# 03_-_General_Part.net
KiCad netlist of a schematic drawn in Altium Designer
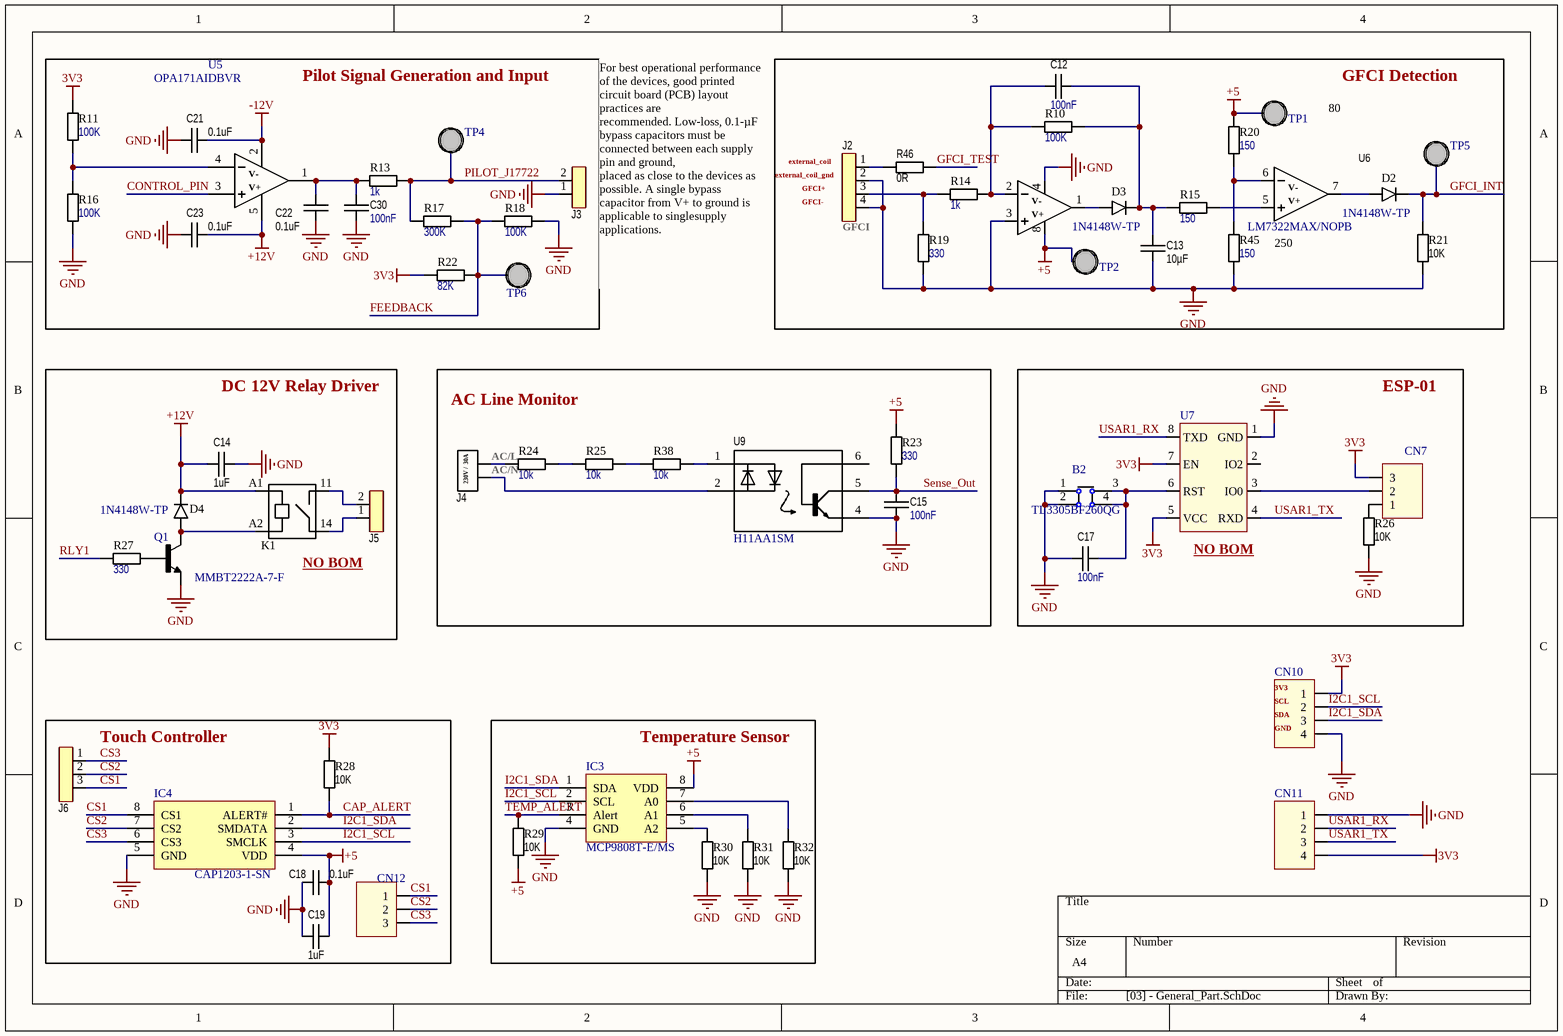
[diagram p0: [03] - General_Part.SchDoc]

(export (version "E")
  (design (tool "Eeschema 10.0.6"))
  (components
    (comp (ref "B2")
      (value "TL3305BF260QG")
      (footprint "Switch")
      (description "Tactile Switch SPST-NO Top Actuated Surface Mount")
      (fields (field (name "MANUFACTURER") "E-Switch"))
      (libsource (lib "myLibrary") (part "SWITCH"))
    )
    (comp (ref "C12")
      (value "100nF")
      (footprint "CAP 0603/1608")
      (description "1µF ±10% 16V Ceramic Capacitor X5R 0603 (1608 Metric)")
      (fields (field (name "PARTNUMBER") "CC0603KRX5R7BB105") (field (name "MANUFACTURER") "Yageo"))
      (libsource (lib "myLibrary") (part "CAPC_100NF_0603_50V"))
    )
    (comp (ref "C13")
      (value "10µF")
      (footprint "CAP 0603/1608")
      (description "10µF ±20% 25V Ceramic Capacitor X5R 0603 (1608 Metric)")
      (fields
        (field (name "PARTNUMBER") "GRM188R61E106MA73D")
        (field (name "MANUFACTURER") "Murata Electronics")
      )
      (libsource (lib "myLibrary") (part "CAPC_10uF_0603_25V"))
    )
    (comp (ref "C14")
      (value "1uF")
      (footprint "CAP 0603/1608")
      (description "1µF ±20% 25V Ceramic Capacitor X5R 0603 (1608 Metric)")
      (fields (field (name "PARTNUMBER") "TMK107BLD105MA-T") (field (name "MANUFACTURER") "Taiyo Yuden"))
      (libsource (lib "myLibrary") (part "CAPC_1uF_0603_25V"))
    )
    (comp (ref "C15")
      (value "100nF")
      (footprint "CAP 0603/1608")
      (description "1µF ±10% 16V Ceramic Capacitor X5R 0603 (1608 Metric)")
      (fields (field (name "PARTNUMBER") "CC0603KRX5R7BB105") (field (name "MANUFACTURER") "Yageo"))
      (libsource (lib "myLibrary") (part "CAPC_100NF_0603_50V"))
    )
    (comp (ref "C17")
      (value "100nF")
      (footprint "CAP 0603/1608")
      (description "1µF ±10% 16V Ceramic Capacitor X5R 0603 (1608 Metric)")
      (fields (field (name "PARTNUMBER") "CC0603KRX5R7BB105") (field (name "MANUFACTURER") "Yageo"))
      (libsource (lib "myLibrary") (part "CAPC_100NF_0603_50V"))
    )
    (comp (ref "C18")
      (value "0.1uF")
      (footprint "CAP 0603/1608")
      (description "0.1µF ±20% 50V Ceramic Capacitor X7R 0603 (1608 Metric)")
      (fields (field (name "PARTNUMBER") "C0603C104M5RACTU") (field (name "MANUFACTURER") "KEMET"))
      (libsource (lib "myLibrary") (part "CAPC_0.1uF_0603_50V"))
    )
    (comp (ref "C19")
      (value "1uF")
      (footprint "CAP 0603/1608")
      (description "1µF ±20% 25V Ceramic Capacitor X5R 0603 (1608 Metric)")
      (fields (field (name "PARTNUMBER") "TMK107BLD105MA-T") (field (name "MANUFACTURER") "Taiyo Yuden"))
      (libsource (lib "myLibrary") (part "CAPC_1uF_0603_25V"))
    )
    (comp (ref "C21")
      (value "0.1uF")
      (footprint "CAP 0603/1608")
      (description "0.1µF ±20% 50V Ceramic Capacitor X7R 0603 (1608 Metric)")
      (fields (field (name "PARTNUMBER") "C0603C104M5RACTU") (field (name "MANUFACTURER") "KEMET"))
      (libsource (lib "myLibrary") (part "CAPC_0.1uF_0603_50V"))
    )
    (comp (ref "C22")
      (value "0.1uF")
      (footprint "CAP 0603/1608")
      (description "0.1µF ±20% 50V Ceramic Capacitor X7R 0603 (1608 Metric)")
      (fields (field (name "PARTNUMBER") "C0603C104M5RACTU") (field (name "MANUFACTURER") "KEMET"))
      (libsource (lib "myLibrary") (part "CAPC_0.1uF_0603_50V"))
    )
    (comp (ref "C23")
      (value "0.1uF")
      (footprint "CAP 0603/1608")
      (description "0.1µF ±20% 50V Ceramic Capacitor X7R 0603 (1608 Metric)")
      (fields (field (name "PARTNUMBER") "C0603C104M5RACTU") (field (name "MANUFACTURER") "KEMET"))
      (libsource (lib "myLibrary") (part "CAPC_0.1uF_0603_50V"))
    )
    (comp (ref "C30")
      (value "100nF")
      (footprint "CAP 0603/1608")
      (description "1µF ±10% 16V Ceramic Capacitor X5R 0603 (1608 Metric)")
      (fields (field (name "PARTNUMBER") "CC0603KRX5R7BB105") (field (name "MANUFACTURER") "Yageo"))
      (libsource (lib "myLibrary") (part "CAPC_100NF_0603_50V"))
    )
    (comp (ref "CN7")
      (value "87220-3")
      (footprint "Terminal_3")
      (description "Connector Header Through Hole 3 position 0.100\" (2.54mm)")
      (fields (field (name "MANUFACTURER") "TE Connectivity AMP Connectors"))
      (libsource (lib "") (part "CONN_3POS_1"))
    )
    (comp (ref "CN10")
      (value "61300411121")
      (footprint "Terminal_4")
      (description "Connector Header Through Hole 4 position 0.100\" (2.54mm)")
      (fields (field (name "MANUFACTURER") "Wurth Electronics Inc."))
      (libsource (lib "myLibrary") (part "CONN_4POS"))
    )
    (comp (ref "CN11")
      (value "61300411121")
      (footprint "Terminal_4")
      (description "Connector Header Through Hole 4 position 0.100\" (2.54mm)")
      (fields (field (name "MANUFACTURER") "Wurth Electronics Inc."))
      (libsource (lib "myLibrary") (part "CONN_4POS"))
    )
    (comp (ref "CN12")
      (value "87220-3")
      (footprint "Terminal_3")
      (description "Connector Header Through Hole 3 position 0.100\" (2.54mm)")
      (fields (field (name "MANUFACTURER") "TE Connectivity AMP Connectors"))
      (libsource (lib "myLibrary") (part "CONN_3POS"))
    )
    (comp (ref "D2")
      (value "1N4148W-TP")
      (footprint "SOD123")
      (description "Diode Standard 100V 150mA Surface Mount SOD-123")
      (fields (field (name "MANUFACTURER") "Micro Commercial Co"))
      (libsource (lib "myLibrary") (part "DIODE _100V_150MA"))
    )
    (comp (ref "D3")
      (value "1N4148W-TP")
      (footprint "SOD123")
      (description "Diode Standard 100V 150mA Surface Mount SOD-123")
      (fields (field (name "MANUFACTURER") "Micro Commercial Co"))
      (libsource (lib "myLibrary") (part "DIODE _100V_150MA"))
    )
    (comp (ref "D4")
      (value "1N4148W-TP")
      (footprint "SOD123")
      (description "Diode Standard 100V 150mA Surface Mount SOD-123")
      (fields (field (name "MANUFACTURER") "Micro Commercial Co"))
      (libsource (lib "myLibrary") (part "DIODE _100V_150MA"))
    )
    (comp (ref "IC3")
      (value "MCP9808T-E/MS")
      (footprint "MSOP-8")
      (description "Temperature Sensor Digital, Local -40°C ~ 125°C 10 b 8-MSOP")
      (fields (field (name "MANUFACTURER") "Microchip Technology"))
      (libsource (lib "myLibrary") (part "MCP9808"))
    )
    (comp (ref "IC4")
      (value "CAP1203-1-SN")
      (footprint "SOIC-8")
      (description "Capacitive Touch Buttons 8-SOIC")
      (fields (field (name "MANUFACTURER") "Microchip Technology"))
      (libsource (lib "myLibrary") (part "CAP1203"))
    )
    (comp (ref "J2")
      (value "1985218")
      (footprint "BLK_04P_3.5MM")
      (description "4 Position Wire to Board Terminal Block 45° (135°) Angle with Board 0.138\" (3.50mm) Through Hole")
      (fields (field (name "MANUFACTURER") "Phoenix Contact"))
      (libsource (lib "myLibrary") (part "BLK_04_3.5"))
    )
    (comp (ref "J3")
      (value "1985195")
      (footprint "BLK_02P_3.5MM")
      (description "2 Position Wire to Board Terminal Block 45° (135°) Angle with Board 0.138\" (3.50mm) Through Hole")
      (fields (field (name "MANUFACTURER") "Phoenix Contact"))
      (libsource (lib "myLibrary") (part "BLK_02_3.5"))
    )
    (comp (ref "J4")
      (value "1868076")
      (footprint "30Amp_Connector")
      (description "2 Position Wire to Board Terminal Block Horizontal with Board 0.300\" (7.62mm) Through Hole")
      (fields (field (name "MANUFACTURER") "Phoenix Contact"))
      (libsource (lib "myLibrary") (part "TERM_BLK_02_30A"))
    )
    (comp (ref "J5")
      (value "1985195")
      (footprint "BLK_02P_3.5MM")
      (description "2 Position Wire to Board Terminal Block 45° (135°) Angle with Board 0.138\" (3.50mm) Through Hole")
      (fields (field (name "MANUFACTURER") "Phoenix Contact"))
      (libsource (lib "myLibrary") (part "BLK_02_3.5"))
    )
    (comp (ref "J6")
      (value "1995279")
      (footprint "BLK_03P_3.5MM")
      (description "3 Position Wire to Board Terminal Block 45° (135°) Angle with Board 0.138\" (3.50mm) Through Hole")
      (fields (field (name "MANUFACTURER") "Phoenix Contact"))
      (libsource (lib "myLibrary") (part "BLK_03_3.5"))
    )
    (comp (ref "K1")
      (value "PCN-112D3MHZ,000")
      (footprint "Relay_PCN")
      (description "General Purpose Relay SPST-NO (1 Form A) 12VDC Coil Through Hole")
      (fields (field (name "MANUFACTURER") "TE Connectivity Potter & Brumfield Relays"))
      (libsource (lib "myLibrary") (part "RL_PCN"))
    )
    (comp (ref "Q1")
      (value "MMBT2222A-7-F")
      (footprint "SOT23-3")
      (description "Bipolar (BJT) Transistor NPN 40V 600mA 300MHz 310mW Surface Mount SOT-23-3")
      (fields (field (name "MANUFACTURER") "Diodes Incorporated"))
      (libsource (lib "myLibrary") (part "NPN_40V_0.6A"))
    )
    (comp (ref "R10")
      (value "100K")
      (footprint "R0603")
      (description "100 kOhms ±0.1% 0.1W, 1/10W Chip Resistor 0603 (1608 Metric) Thin Film")
      (fields (field (name "PARTNUMBER") "RT0603BRD07100KL") (field (name "MANUFACTURER") "Yageo"))
      (libsource (lib "") (part "RES_100k_0603_0.1%_1"))
    )
    (comp (ref "R11")
      (value "100K")
      (footprint "R0603")
      (description "100 kOhms ±0.1% 0.1W, 1/10W Chip Resistor 0603 (1608 Metric) Thin Film")
      (fields (field (name "PARTNUMBER") "RT0603BRD07100KL") (field (name "MANUFACTURER") "Yageo"))
      (libsource (lib "myLibrary") (part "RES_100k_0603_0.1%"))
    )
    (comp (ref "R13")
      (value "1k")
      (footprint "R0603")
      (description "1 kOhms ±5% 0.1W, 1/10W Chip Resistor 0603 (1608 Metric) Moisture Resistant Thick Film\r\nDo")
      (fields (field (name "PARTNUMBER") "RC0603JR-071KL") (field (name "MANUFACTURER") "Yageo"))
      (libsource (lib "myLibrary") (part "RES_1k_0603_5%"))
    )
    (comp (ref "R14")
      (value "1k")
      (footprint "R0603")
      (description "1 kOhms ±5% 0.1W, 1/10W Chip Resistor 0603 (1608 Metric) Moisture Resistant Thick Film\r\nDo")
      (fields (field (name "PARTNUMBER") "RC0603JR-071KL") (field (name "MANUFACTURER") "Yageo"))
      (libsource (lib "myLibrary") (part "RES_1k_0603_5%"))
    )
    (comp (ref "R15")
      (value "150")
      (footprint "R0603")
      (description "150 Ohms ±5% 0.1W, 1/10W Chip Resistor 0603 (1608 Metric) Moisture Resistant Thick Film")
      (fields (field (name "PARTNUMBER") "RC0603JR-07150RL") (field (name "MANUFACTURER") "Yageo"))
      (libsource (lib "myLibrary") (part "RES_150_0603_5%"))
    )
    (comp (ref "R16")
      (value "100K")
      (footprint "R0603")
      (description "100 kOhms ±0.1% 0.1W, 1/10W Chip Resistor 0603 (1608 Metric) Thin Film")
      (fields (field (name "PARTNUMBER") "RT0603BRD07100KL") (field (name "MANUFACTURER") "Yageo"))
      (libsource (lib "myLibrary") (part "RES_100k_0603_0.1%"))
    )
    (comp (ref "R17")
      (value "300K")
      (footprint "R0603")
      (description "300 kOhms ±5% 0.1W, 1/10W Chip Resistor 0603 (1608 Metric) Moisture Resistant Thick Film")
      (fields (field (name "PARTNUMBER") "RC0603JR-07300KL") (field (name "MANUFACTURER") "Yageo"))
      (libsource (lib "myLibrary") (part "RES_300K_0603_1%"))
    )
    (comp (ref "R18")
      (value "100K")
      (footprint "R0603")
      (description "100 kOhms ±0.1% 0.1W, 1/10W Chip Resistor 0603 (1608 Metric) Thin Film")
      (fields (field (name "PARTNUMBER") "RT0603BRD07100KL") (field (name "MANUFACTURER") "Yageo"))
      (libsource (lib "") (part "RES_100k_0603_0.1%_1"))
    )
    (comp (ref "R19")
      (value "330")
      (footprint "R0603")
      (description "330 Ohms ±1% 0.1W, 1/10W Chip Resistor 0603 (1608 Metric) Moisture Resistant Thick Film")
      (fields (field (name "PARTNUMBER") "RC0603FR-07330RL") (field (name "MANUFACTURER") "Yageo"))
      (libsource (lib "") (part "RES_330_0603_1%_1"))
    )
    (comp (ref "R20")
      (value "150")
      (footprint "R0603")
      (description "150 Ohms ±5% 0.1W, 1/10W Chip Resistor 0603 (1608 Metric) Moisture Resistant Thick Film")
      (fields (field (name "PARTNUMBER") "RC0603JR-07150RL") (field (name "MANUFACTURER") "Yageo"))
      (libsource (lib "") (part "RES_150_0603_5%_1"))
    )
    (comp (ref "R21")
      (value "10K")
      (footprint "R0603")
      (fields (field (name "PARTNUMBER") "ESR03EZPF1002") (field (name "MANUFACTURER") "Rohm Semiconductor"))
      (libsource (lib "myLibrary") (part "RES_10K"))
    )
    (comp (ref "R22")
      (value "82K")
      (footprint "R0603")
      (description "82 kOhms ±0.1% 0.1W, 1/10W Chip Resistor 0603 (1608 Metric) Thin Film")
      (fields (field (name "PARTNUMBER") "RT0603BRD0782KL") (field (name "MANUFACTURER") "Yageo"))
      (libsource (lib "myLibrary") (part "RES_82K_0603_0.1%"))
    )
    (comp (ref "R23")
      (value "330")
      (footprint "R0603")
      (description "330 Ohms ±1% 0.1W, 1/10W Chip Resistor 0603 (1608 Metric) Moisture Resistant Thick Film")
      (fields (field (name "PARTNUMBER") "RC0603FR-07330RL") (field (name "MANUFACTURER") "Yageo"))
      (libsource (lib "") (part "RES_330_0603_1%_1"))
    )
    (comp (ref "R24")
      (value "10k")
      (footprint "R1206")
      (description "10 kOhms ±1% 0.25W, 1/4W Chip Resistor 1206 (3216 Metric) Automotive AEC-Q200 Thick Film")
      (fields
        (field (name "PARTNUMBER") "ERJ-8ENF1002V")
        (field (name "MANUFACTURER") "Panasonic Electronic Components")
      )
      (libsource (lib "myLibrary") (part "RES_10k_1206_1%"))
    )
    (comp (ref "R25")
      (value "10k")
      (footprint "R1206")
      (description "10 kOhms ±1% 0.25W, 1/4W Chip Resistor 1206 (3216 Metric) Automotive AEC-Q200 Thick Film")
      (fields
        (field (name "PARTNUMBER") "ERJ-8ENF1002V")
        (field (name "MANUFACTURER") "Panasonic Electronic Components")
      )
      (libsource (lib "myLibrary") (part "RES_10k_1206_1%"))
    )
    (comp (ref "R26")
      (value "10K")
      (footprint "R0603")
      (fields (field (name "PARTNUMBER") "ESR03EZPF1002") (field (name "MANUFACTURER") "Rohm Semiconductor"))
      (libsource (lib "") (part "RES_10K_1"))
    )
    (comp (ref "R27")
      (value "330")
      (footprint "R0603")
      (description "330 Ohms ±1% 0.1W, 1/10W Chip Resistor 0603 (1608 Metric) Moisture Resistant Thick Film")
      (fields (field (name "PARTNUMBER") "RC0603FR-07330RL") (field (name "MANUFACTURER") "Yageo"))
      (libsource (lib "myLibrary") (part "RES_330_0603_1%"))
    )
    (comp (ref "R28")
      (value "10K")
      (footprint "R0603")
      (fields (field (name "PARTNUMBER") "ESR03EZPF1002") (field (name "MANUFACTURER") "Rohm Semiconductor"))
      (libsource (lib "myLibrary") (part "RES_10K"))
    )
    (comp (ref "R29")
      (value "10K")
      (footprint "R0603")
      (fields (field (name "PARTNUMBER") "ESR03EZPF1002") (field (name "MANUFACTURER") "Rohm Semiconductor"))
      (libsource (lib "myLibrary") (part "RES_10K"))
    )
    (comp (ref "R30")
      (value "10K")
      (footprint "R0603")
      (fields (field (name "PARTNUMBER") "ESR03EZPF1002") (field (name "MANUFACTURER") "Rohm Semiconductor"))
      (libsource (lib "myLibrary") (part "RES_10K"))
    )
    (comp (ref "R31")
      (value "10K")
      (footprint "R0603")
      (fields (field (name "PARTNUMBER") "ESR03EZPF1002") (field (name "MANUFACTURER") "Rohm Semiconductor"))
      (libsource (lib "myLibrary") (part "RES_10K"))
    )
    (comp (ref "R32")
      (value "10K")
      (footprint "R0603")
      (fields (field (name "PARTNUMBER") "ESR03EZPF1002") (field (name "MANUFACTURER") "Rohm Semiconductor"))
      (libsource (lib "myLibrary") (part "RES_10K"))
    )
    (comp (ref "R38")
      (value "10k")
      (footprint "R1206")
      (description "10 kOhms ±1% 0.25W, 1/4W Chip Resistor 1206 (3216 Metric) Automotive AEC-Q200 Thick Film")
      (fields
        (field (name "PARTNUMBER") "ERJ-8ENF1002V")
        (field (name "MANUFACTURER") "Panasonic Electronic Components")
      )
      (libsource (lib "myLibrary") (part "RES_10k_1206_1%"))
    )
    (comp (ref "R45")
      (value "150")
      (footprint "R0603")
      (description "150 Ohms ±5% 0.1W, 1/10W Chip Resistor 0603 (1608 Metric) Moisture Resistant Thick Film")
      (fields (field (name "PARTNUMBER") "RC0603JR-07150RL") (field (name "MANUFACTURER") "Yageo"))
      (libsource (lib "") (part "RES_150_0603_5%_1"))
    )
    (comp (ref "R46")
      (value "0R")
      (footprint "R0603")
      (description "RES 0R 0603 JUMPER")
      (fields (field (name "PARTNUMBER") "RC0603JR-070RL") (field (name "MANUFACTURER") "Yageo"))
      (libsource (lib "myLibrary") (part "RES_0R_0603_JUMPER"))
    )
    (comp (ref "TP1") (value "Test_Point") (footprint "TP") (libsource (lib "myLibrary") (part "Test_Point")))
    (comp (ref "TP2") (value "Test_Point") (footprint "TP") (libsource (lib "myLibrary") (part "Test_Point")))
    (comp (ref "TP4") (value "Test_Point") (footprint "TP") (libsource (lib "myLibrary") (part "Test_Point")))
    (comp (ref "TP5") (value "Test_Point") (footprint "TP") (libsource (lib "myLibrary") (part "Test_Point")))
    (comp (ref "TP6") (value "Test_Point") (footprint "TP") (libsource (lib "myLibrary") (part "Test_Point")))
    (comp (ref "U5")
      (value "OPA171AIDBVR")
      (footprint "SOT-23-5")
      (description "General Purpose Amplifier 1 Circuit Rail-to-Rail SOT-23-5")
      (fields (field (name "MANUFACTURER") "Texas Instruments"))
      (libsource (lib "myLibrary") (part "OPA171"))
    )
    (comp (ref "U6")
      (value "LM7322MAX/NOPB")
      (footprint "SOIC-8")
      (description "General Purpose Amplifier 2 Circuit Rail-to-Rail 8-SOIC")
      (fields (field (name "MANUFACTURER") "Texas Instruments"))
      (libsource (lib "myLibrary") (part "OP_LM7322"))
    )
    (comp (ref "U7")
      (value "317060016")
      (footprint "Terminal_ESP")
      (description "WiFi 802.11b/g/n Transceiver Module 2.4GHz ~ 2.48GHz Integrated, Trace Through Hole")
      (fields (field (name "MANUFACTURER") "Seeed Technology Co., Ltd"))
      (libsource (lib "myLibrary") (part "ESP-01"))
    )
    (comp (ref "U9")
      (value "H11AA1SM")
      (footprint "6-SMD")
      (description "Optoisolator Transistor with Base Output 4170Vrms 1 Channel 6-SMD")
      (fields (field (name "MANUFACTURER") "ON Semiconductor"))
      (libsource (lib "myLibrary") (part "Opto_H11AA1"))
    )
  )
  (nets
    (net (code "1") (name "+5") (class "Default")
      (node (ref "C18") (pin "2") (pintype "passive"))
      (node (ref "C19") (pin "2") (pintype "passive"))
      (node (ref "IC3") (pin "8") (pinfunction "VDD_8") (pintype "passive"))
      (node (ref "IC4") (pin "4") (pinfunction "VDD_4") (pintype "passive"))
      (node (ref "R20") (pin "1") (pinfunction "1_1") (pintype "passive"))
      (node (ref "R23") (pin "1") (pinfunction "1_1") (pintype "passive"))
      (node (ref "R29") (pin "2") (pinfunction "2_2") (pintype "passive"))
      (node (ref "TP1") (pin "1") (pinfunction "1_1") (pintype "passive"))
      (node (ref "TP2") (pin "1") (pinfunction "1_1") (pintype "passive"))
      (node (ref "U6") (pin "8") (pinfunction "V+_8") (pintype "power_in"))
    )
    (net (code "2") (name "+12V") (class "Default")
      (node (ref "C14") (pin "1") (pintype "passive"))
      (node (ref "C23") (pin "1") (pintype "passive"))
      (node (ref "D4") (pin "C") (pinfunction "C_C") (pintype "passive"))
      (node (ref "K1") (pin "A1") (pinfunction "A1_A1") (pintype "passive"))
      (node (ref "U5") (pin "5") (pinfunction "VDD_5") (pintype "power_in"))
    )
    (net (code "3") (name "-12V") (class "Default")
      (node (ref "C21") (pin "1") (pintype "passive"))
      (node (ref "U5") (pin "2") (pinfunction "GND_2") (pintype "power_in"))
    )
    (net (code "4") (name "/CAP_ALERT") (class "Default")
      (node (ref "IC4") (pin "1") (pinfunction "ALERT#_1") (pintype "passive"))
      (node (ref "R28") (pin "2") (pinfunction "2_2") (pintype "passive"))
    )
    (net (code "5") (name "/CONTROL_PIN") (class "Default")
      (node (ref "U5") (pin "3") (pinfunction "IN+_3") (pintype "passive"))
    )
    (net (code "6") (name "/CS1") (class "Default")
      (node (ref "CN12") (pin "1") (pinfunction "1_1") (pintype "passive"))
      (node (ref "IC4") (pin "8") (pinfunction "CS1_8") (pintype "passive"))
      (node (ref "J6") (pin "3") (pintype "passive"))
    )
    (net (code "7") (name "/CS2") (class "Default")
      (node (ref "CN12") (pin "2") (pinfunction "2_2") (pintype "passive"))
      (node (ref "IC4") (pin "7") (pinfunction "CS2_7") (pintype "passive"))
      (node (ref "J6") (pin "2") (pintype "passive"))
    )
    (net (code "8") (name "/CS3") (class "Default")
      (node (ref "CN12") (pin "3") (pinfunction "3_3") (pintype "passive"))
      (node (ref "IC4") (pin "6") (pinfunction "CS3_6") (pintype "passive"))
      (node (ref "J6") (pin "1") (pintype "passive"))
    )
    (net (code "9") (name "/FEEDBACK") (class "Default")
      (node (ref "R17") (pin "2") (pinfunction "2_2") (pintype "passive"))
      (node (ref "R18") (pin "1") (pinfunction "1_1") (pintype "passive"))
      (node (ref "R22") (pin "2") (pinfunction "2_2") (pintype "passive"))
      (node (ref "TP6") (pin "1") (pinfunction "1_1") (pintype "passive"))
    )
    (net (code "10") (name "/GFCI_INT") (class "Default")
      (node (ref "D2") (pin "C") (pinfunction "C_C") (pintype "passive"))
      (node (ref "R21") (pin "1") (pinfunction "1_1") (pintype "passive"))
      (node (ref "TP5") (pin "1") (pinfunction "1_1") (pintype "passive"))
    )
    (net (code "11") (name "/GFCI_TEST") (class "Default")
      (node (ref "R46") (pin "2") (pinfunction "2_2") (pintype "passive"))
    )
    (net (code "12") (name "/I2C1_SCL") (class "Default")
      (node (ref "CN10") (pin "2") (pinfunction "2_2") (pintype "passive"))
      (node (ref "IC3") (pin "2") (pinfunction "SCL_2") (pintype "passive"))
      (node (ref "IC4") (pin "3") (pinfunction "SMCLK_3") (pintype "passive"))
    )
    (net (code "13") (name "/I2C1_SDA") (class "Default")
      (node (ref "CN10") (pin "3") (pinfunction "3_3") (pintype "passive"))
      (node (ref "IC3") (pin "1") (pinfunction "SDA_1") (pintype "passive"))
      (node (ref "IC4") (pin "2") (pinfunction "SMDATA_2") (pintype "passive"))
    )
    (net (code "14") (name "/PILOT_J17722") (class "Default")
      (node (ref "J3") (pin "2") (pintype "passive"))
      (node (ref "R13") (pin "2") (pinfunction "2_2") (pintype "passive"))
      (node (ref "R17") (pin "1") (pinfunction "1_1") (pintype "passive"))
      (node (ref "TP4") (pin "1") (pinfunction "1_1") (pintype "passive"))
    )
    (net (code "15") (name "/RLY1") (class "Default")
      (node (ref "R27") (pin "1") (pinfunction "1_1") (pintype "passive"))
    )
    (net (code "16") (name "/Sense_Out") (class "Default")
      (node (ref "C15") (pin "1") (pintype "passive"))
      (node (ref "R23") (pin "2") (pinfunction "2_2") (pintype "passive"))
      (node (ref "U9") (pin "5") (pinfunction "C_5") (pintype "passive"))
    )
    (net (code "17") (name "/TEMP_ALERT") (class "Default")
      (node (ref "IC3") (pin "3") (pinfunction "Alert_3") (pintype "passive"))
      (node (ref "R29") (pin "1") (pinfunction "1_1") (pintype "passive"))
    )
    (net (code "18") (name "/USAR1_RX") (class "Default")
      (node (ref "CN11") (pin "2") (pinfunction "2_2") (pintype "passive"))
      (node (ref "U7") (pin "8") (pinfunction "TXD_8") (pintype "passive"))
    )
    (net (code "19") (name "/USAR1_TX") (class "Default")
      (node (ref "CN11") (pin "3") (pinfunction "3_3") (pintype "passive"))
      (node (ref "U7") (pin "4") (pinfunction "RXD_4") (pintype "passive"))
    )
    (net (code "20") (name "3V3") (class "Default")
      (node (ref "CN10") (pin "1") (pinfunction "1_1") (pintype "passive"))
      (node (ref "CN11") (pin "4") (pinfunction "4_4") (pintype "passive"))
      (node (ref "CN7") (pin "3") (pinfunction "3_3") (pintype "passive"))
      (node (ref "R11") (pin "1") (pinfunction "1_1") (pintype "passive"))
      (node (ref "R22") (pin "1") (pinfunction "1_1") (pintype "passive"))
      (node (ref "R28") (pin "1") (pinfunction "1_1") (pintype "passive"))
      (node (ref "U7") (pin "5") (pinfunction "VCC_5") (pintype "passive"))
      (node (ref "U7") (pin "7") (pinfunction "EN_7") (pintype "passive"))
    )
    (net (code "21") (name "GND") (class "Default")
      (node (ref "B2") (pin "1") (pinfunction "1_1") (pintype "passive"))
      (node (ref "B2") (pin "2") (pinfunction "2_2") (pintype "passive"))
      (node (ref "C13") (pin "2") (pintype "passive"))
      (node (ref "C14") (pin "2") (pintype "passive"))
      (node (ref "C15") (pin "2") (pintype "passive"))
      (node (ref "C17") (pin "1") (pintype "passive"))
      (node (ref "C18") (pin "1") (pintype "passive"))
      (node (ref "C19") (pin "1") (pintype "passive"))
      (node (ref "C21") (pin "2") (pintype "passive"))
      (node (ref "C22") (pin "2") (pintype "passive"))
      (node (ref "C23") (pin "2") (pintype "passive"))
      (node (ref "C30") (pin "2") (pintype "passive"))
      (node (ref "CN10") (pin "4") (pinfunction "4_4") (pintype "passive"))
      (node (ref "CN11") (pin "1") (pinfunction "1_1") (pintype "passive"))
      (node (ref "IC3") (pin "4") (pinfunction "GND_4") (pintype "passive"))
      (node (ref "IC4") (pin "5") (pinfunction "GND_5") (pintype "passive"))
      (node (ref "J2") (pin "2") (pintype "passive"))
      (node (ref "J2") (pin "4") (pintype "passive"))
      (node (ref "J3") (pin "1") (pintype "passive"))
      (node (ref "Q1") (pin "E") (pinfunction "E_E") (pintype "passive"))
      (node (ref "R16") (pin "2") (pinfunction "2_2") (pintype "passive"))
      (node (ref "R18") (pin "2") (pinfunction "2_2") (pintype "passive"))
      (node (ref "R19") (pin "2") (pinfunction "2_2") (pintype "passive"))
      (node (ref "R21") (pin "2") (pinfunction "2_2") (pintype "passive"))
      (node (ref "R26") (pin "1") (pinfunction "1_1") (pintype "passive"))
      (node (ref "R30") (pin "2") (pinfunction "2_2") (pintype "passive"))
      (node (ref "R31") (pin "2") (pinfunction "2_2") (pintype "passive"))
      (node (ref "R32") (pin "2") (pinfunction "2_2") (pintype "passive"))
      (node (ref "R45") (pin "2") (pinfunction "2_2") (pintype "passive"))
      (node (ref "U6") (pin "3") (pinfunction "INA+_3") (pintype "passive"))
      (node (ref "U6") (pin "4") (pinfunction "V-_4") (pintype "passive"))
      (node (ref "U7") (pin "1") (pinfunction "GND_1") (pintype "passive"))
      (node (ref "U9") (pin "4") (pinfunction "E_4") (pintype "passive"))
    )
    (net (code "22") (name "Net-(C12-Pad2)") (class "Default")
      (node (ref "C12") (pin "2") (pintype "passive"))
      (node (ref "C13") (pin "1") (pintype "passive"))
      (node (ref "D3") (pin "C") (pinfunction "C_C") (pintype "passive"))
      (node (ref "R10") (pin "2") (pinfunction "2_2") (pintype "passive"))
      (node (ref "R15") (pin "1") (pinfunction "1_1") (pintype "passive"))
    )
    (net (code "23") (name "Net-(CN7-Pad1)") (class "Default")
      (node (ref "CN7") (pin "1") (pinfunction "1_1") (pintype "passive"))
      (node (ref "R26") (pin "2") (pinfunction "2_2") (pintype "passive"))
    )
    (net (code "24") (name "Net-(D4-PadA)") (class "Default")
      (node (ref "D4") (pin "A") (pinfunction "A_A") (pintype "passive"))
      (node (ref "K1") (pin "A2") (pinfunction "A2_A2") (pintype "passive"))
      (node (ref "Q1") (pin "C") (pinfunction "C_C") (pintype "passive"))
    )
    (net (code "25") (name "Net-(IC3-A0)") (class "Default")
      (node (ref "IC3") (pin "7") (pinfunction "A0_7") (pintype "passive"))
      (node (ref "R32") (pin "1") (pinfunction "1_1") (pintype "passive"))
    )
    (net (code "26") (name "Net-(IC3-A1)") (class "Default")
      (node (ref "IC3") (pin "6") (pinfunction "A1_6") (pintype "passive"))
      (node (ref "R31") (pin "1") (pinfunction "1_1") (pintype "passive"))
    )
    (net (code "27") (name "Net-(IC3-A2)") (class "Default")
      (node (ref "IC3") (pin "5") (pinfunction "A2_5") (pintype "passive"))
      (node (ref "R30") (pin "1") (pinfunction "1_1") (pintype "passive"))
    )
    (net (code "28") (name "Net-(J2-Pad1)") (class "Default")
      (node (ref "J2") (pin "1") (pintype "passive"))
      (node (ref "R46") (pin "1") (pinfunction "1_1") (pintype "passive"))
    )
    (net (code "29") (name "Net-(J2-Pad3)") (class "Default")
      (node (ref "J2") (pin "3") (pintype "passive"))
      (node (ref "R14") (pin "1") (pinfunction "1_1") (pintype "passive"))
      (node (ref "R19") (pin "1") (pinfunction "1_1") (pintype "passive"))
    )
    (net (code "30") (name "Net-(J4-Pad2)") (class "Default")
      (node (ref "J4") (pin "2") (pintype "passive"))
      (node (ref "R24") (pin "1") (pinfunction "1_1") (pintype "passive"))
    )
    (net (code "31") (name "Net-(J5-Pad1)") (class "Default")
      (node (ref "J5") (pin "1") (pintype "passive"))
      (node (ref "K1") (pin "14") (pinfunction "14_14") (pintype "passive"))
    )
    (net (code "32") (name "Net-(J5-Pad2)") (class "Default")
      (node (ref "J5") (pin "2") (pintype "passive"))
      (node (ref "K1") (pin "11") (pinfunction "11_11") (pintype "passive"))
    )
    (net (code "33") (name "Net-(Q1-PadB)") (class "Default")
      (node (ref "Q1") (pin "B") (pinfunction "B_B") (pintype "passive"))
      (node (ref "R27") (pin "2") (pinfunction "2_2") (pintype "passive"))
    )
    (net (code "34") (name "Net-(R24-Pad2)") (class "Default")
      (node (ref "R24") (pin "2") (pinfunction "2_2") (pintype "passive"))
      (node (ref "R25") (pin "1") (pinfunction "1_1") (pintype "passive"))
    )
    (net (code "35") (name "Net-(R25-Pad2)") (class "Default")
      (node (ref "R25") (pin "2") (pinfunction "2_2") (pintype "passive"))
      (node (ref "R38") (pin "1") (pinfunction "1_1") (pintype "passive"))
    )
    (net (code "36") (name "Net-(U5-1OUT)") (class "Default")
      (node (ref "C22") (pin "1") (pintype "passive"))
      (node (ref "C30") (pin "1") (pintype "passive"))
      (node (ref "R13") (pin "1") (pinfunction "1_1") (pintype "passive"))
      (node (ref "U5") (pin "1") (pinfunction "1OUT_1") (pintype "passive"))
    )
    (net (code "37") (name "Net-(U5-IN-)") (class "Default")
      (node (ref "R11") (pin "2") (pinfunction "2_2") (pintype "passive"))
      (node (ref "R16") (pin "1") (pinfunction "1_1") (pintype "passive"))
      (node (ref "U5") (pin "4") (pinfunction "IN-_4") (pintype "passive"))
    )
    (net (code "38") (name "Net-(U6-INA-)") (class "Default")
      (node (ref "C12") (pin "1") (pintype "passive"))
      (node (ref "R10") (pin "1") (pinfunction "1_1") (pintype "passive"))
      (node (ref "R14") (pin "2") (pinfunction "2_2") (pintype "passive"))
      (node (ref "U6") (pin "2") (pinfunction "INA-_2") (pintype "passive"))
    )
    (net (code "39") (name "Net-(U6-INB+)") (class "Default")
      (node (ref "R15") (pin "2") (pinfunction "2_2") (pintype "passive"))
      (node (ref "U6") (pin "5") (pinfunction "INB+_5") (pintype "passive"))
    )
    (net (code "40") (name "Net-(U6-INB-)") (class "Default")
      (node (ref "R20") (pin "2") (pinfunction "2_2") (pintype "passive"))
      (node (ref "R45") (pin "1") (pinfunction "1_1") (pintype "passive"))
      (node (ref "U6") (pin "6") (pinfunction "INB-_6") (pintype "passive"))
    )
    (net (code "41") (name "Net-(U6-OUTA)") (class "Default")
      (node (ref "D3") (pin "A") (pinfunction "A_A") (pintype "passive"))
      (node (ref "U6") (pin "1") (pinfunction "OUTA_1") (pintype "passive"))
    )
    (net (code "42") (name "Net-(U6-OUTB)") (class "Default")
      (node (ref "D2") (pin "A") (pinfunction "A_A") (pintype "passive"))
      (node (ref "U6") (pin "7") (pinfunction "OUTB_7") (pintype "passive"))
    )
    (net (code "43") (name "Net-(U7-IO0)") (class "Default")
      (node (ref "CN7") (pin "2") (pinfunction "2_2") (pintype "passive"))
      (node (ref "U7") (pin "3") (pinfunction "IO0_3") (pintype "passive"))
    )
    (net (code "44") (name "Net-(U7-RST)") (class "Default")
      (node (ref "B2") (pin "3") (pinfunction "3_3") (pintype "passive"))
      (node (ref "B2") (pin "4") (pinfunction "4_4") (pintype "passive"))
      (node (ref "C17") (pin "2") (pintype "passive"))
      (node (ref "U7") (pin "6") (pinfunction "RST_6") (pintype "passive"))
    )
    (net (code "45") (name "Net-(U9-A{slash}C)") (class "Default")
      (node (ref "R38") (pin "2") (pinfunction "2_2") (pintype "passive"))
      (node (ref "U9") (pin "1") (pinfunction "A/C_1") (pintype "passive"))
    )
    (net (code "46") (name "Net-(U9-C{slash}A)") (class "Default")
      (node (ref "J4") (pin "1") (pintype "passive"))
      (node (ref "U9") (pin "2") (pinfunction "C/A_2") (pintype "passive"))
    )
    (net (code "47") (name "unconnected-(U7-IO2-Pad2)") (class "Default")
      (node (ref "U7") (pin "2") (pinfunction "IO2_2") (pintype "passive"))
    )
    (net (code "48") (name "unconnected-(U9-B-Pad6)") (class "Default")
      (node (ref "U9") (pin "6") (pinfunction "B_6") (pintype "passive"))
    )
  )
)
